# MainCircuit.net
KiCad netlist of a schematic drawn in Altium Designer
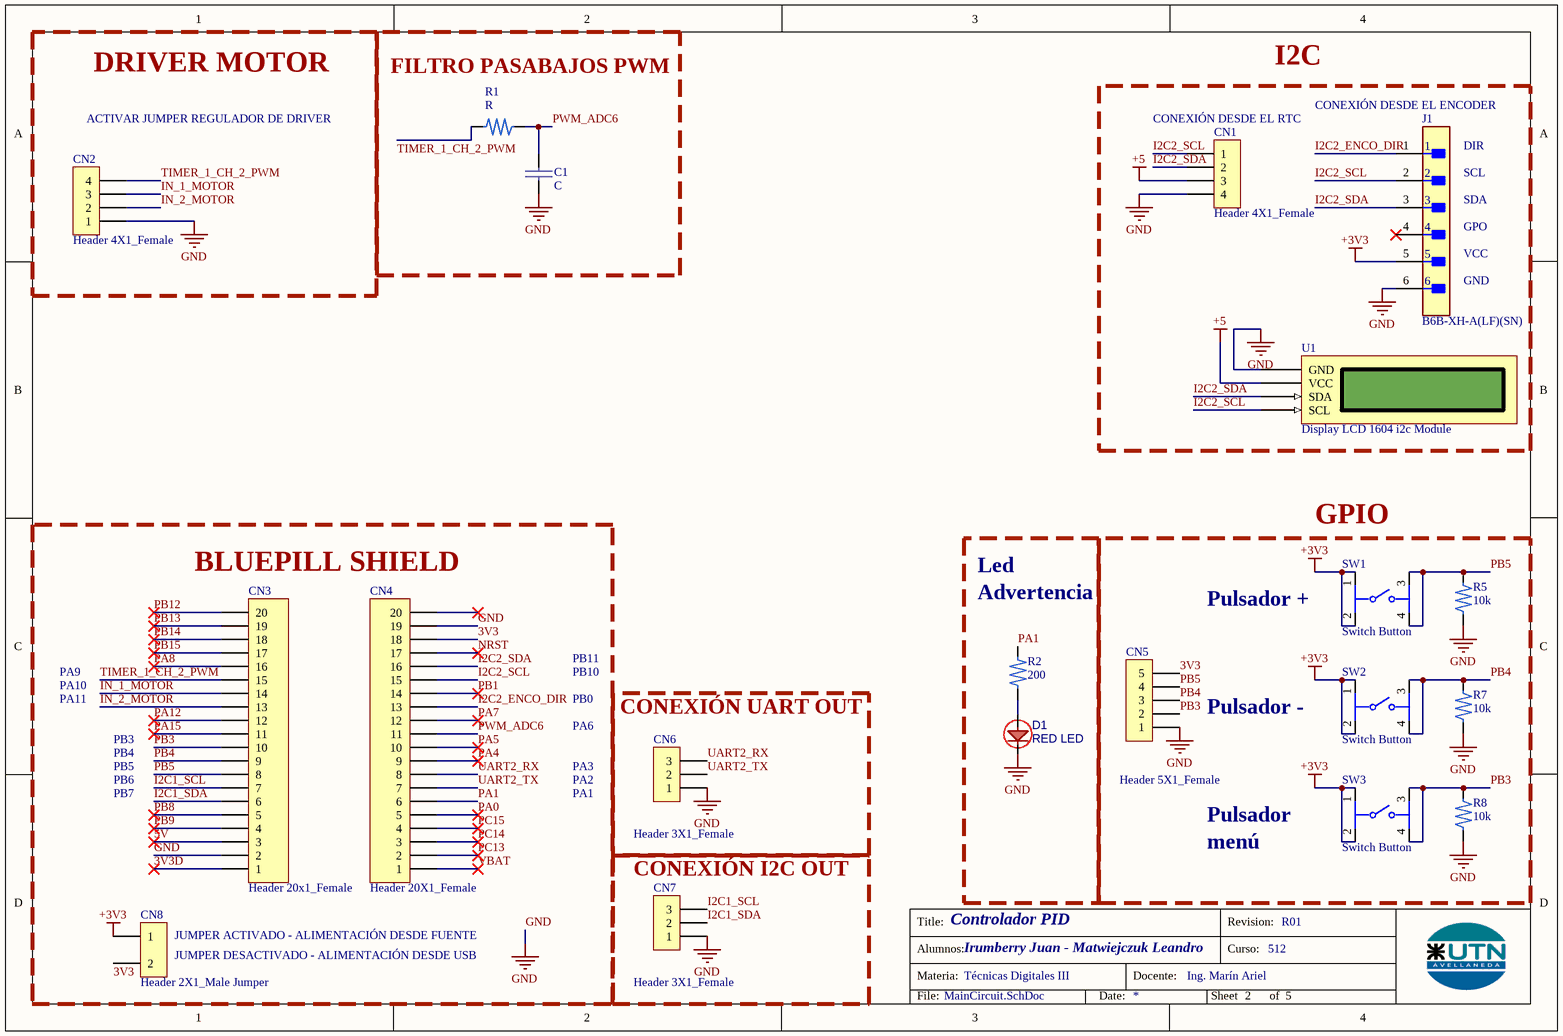
[diagram p0: MainCircuit.SchDoc]

(export (version "E")
  (design (tool "Eeschema 10.0.6"))
  (components
    (comp (ref "C1")
      (value "C")
      (footprint "CAP_Axial_0.2mm")
      (description "Non-Polarized Capacitor")
      (libsource (lib "ProyectoTD3") (part "CAP_NP"))
    )
    (comp (ref "CN1")
      (value "Header 4X1_Female")
      (footprint "1*4P_FEMALE")
      (description "Header, 4-Pin, Single row,female")
      (fields (field (name "PUBLISHER") "Altium Limited"))
      (libsource (lib "") (part "Header 4X1_Female_1"))
    )
    (comp (ref "CN2")
      (value "Header 4X1_Female")
      (footprint "1*4P_FEMALE")
      (description "Header, 4-Pin, Single row,female")
      (fields (field (name "PUBLISHER") "Altium Limited"))
      (libsource (lib "ProyectoTD3") (part "Header 4X1_Female"))
    )
    (comp (ref "CN3")
      (value "Header 20x1_Female")
      (footprint "1*20P_FEMALE")
      (description "Header, 16-Pin, Single row,female")
      (libsource (lib "ProyectoTD3") (part "Header 20x1_Female"))
    )
    (comp (ref "CN4")
      (value "Header 20X1_Female")
      (footprint "1*20P_FEMALE")
      (description "Header, 16-Pin, Single row,female")
      (libsource (lib "") (part "Header 20x1_Female_1"))
    )
    (comp (ref "CN5")
      (value "Header 5X1_Female")
      (footprint "1*5P_FEMALE")
      (description "Header, 5-Pin, Single row,female")
      (fields (field (name "PUBLISHER") "Altium Limited"))
      (libsource (lib "ProyectoTD3") (part "Header 5X1_Female"))
    )
    (comp (ref "CN6")
      (value "Header 3X1_Female")
      (footprint "1*3P_FEMALE")
      (description "Header, 3-Pin, Single row,female")
      (fields (field (name "PUBLISHER") "Altium Limited"))
      (libsource (lib "ProyectoTD3") (part "Header 3X1_Female"))
    )
    (comp (ref "CN7")
      (value "Header 3X1_Female")
      (footprint "1*3P_FEMALE")
      (description "Header, 3-Pin, Single row,female")
      (fields (field (name "PUBLISHER") "Altium Limited"))
      (libsource (lib "ProyectoTD3") (part "Header 3X1_Female"))
    )
    (comp (ref "CN8")
      (value "Header 2X1_Male Jumper")
      (footprint "JUMPER 2x1 PIN")
      (description "Header, 2-Pin, Single row,male")
      (fields (field (name "PUBLISHER") "Altium Limited"))
      (libsource (lib "ProyectoTD3") (part "Jumper 2 Pin"))
    )
    (comp (ref "D1")
      (value "RED LED")
      (footprint "LED_DIODE_3.9mm")
      (description "LED")
      (libsource (lib "ProyectoSchlib1") (part "LED"))
    )
    (comp (ref "J1")
      (value "B6B-XH-A(LF)(SN)")
      (footprint "JST 6 PIN CONNECTOR")
      (description "CONN HEADER VERT 6POS 2.5MM")
      (libsource (lib "ProyectoTD3") (part "JST 6 PIN"))
    )
    (comp (ref "R1")
      (value "R")
      (footprint "RES_AXIAL_3.2_6MM")
      (description "Through-hole Resistor")
      (libsource (lib "ProyectoTD3") (part "RES"))
    )
    (comp (ref "R2")
      (value "200")
      (footprint "RES_AXIAL_3.2_6MM")
      (description "Through-hole Resistor")
      (libsource (lib "ProyectoTD3") (part "RES"))
    )
    (comp (ref "R5")
      (value "10k")
      (footprint "RES_AXIAL_3.2_6MM")
      (description "Through-hole Resistor")
      (libsource (lib "ProyectoTD3") (part "RES"))
    )
    (comp (ref "R7")
      (value "10k")
      (footprint "RES_AXIAL_3.2_6MM")
      (description "Through-hole Resistor")
      (libsource (lib "ProyectoTD3") (part "RES"))
    )
    (comp (ref "R8")
      (value "10k")
      (footprint "RES_AXIAL_3.2_6MM")
      (description "Through-hole Resistor")
      (libsource (lib "ProyectoTD3") (part "RES"))
    )
    (comp (ref "SW1")
      (value "Switch Button")
      (footprint "SWITCH")
      (description "SWITCH TACTILE SPST-NO 0.05A 24V")
      (fields
        (field (name "OCTOPART") "https://octopart.com/1-1825910-4-te+connectivity-42270468")
        (field (name "MANUFACTURER") "TE Connectivity")
      )
      (libsource (lib "ProyectoTD3") (part "Switch Button"))
    )
    (comp (ref "SW2")
      (value "Switch Button")
      (footprint "SWITCH")
      (description "SWITCH TACTILE SPST-NO 0.05A 24V")
      (fields
        (field (name "OCTOPART") "https://octopart.com/1-1825910-4-te+connectivity-42270468")
        (field (name "MANUFACTURER") "TE Connectivity")
      )
      (libsource (lib "ProyectoTD3") (part "Switch Button"))
    )
    (comp (ref "SW3")
      (value "Switch Button")
      (footprint "SWITCH")
      (description "SWITCH TACTILE SPST-NO 0.05A 24V")
      (fields
        (field (name "OCTOPART") "https://octopart.com/1-1825910-4-te+connectivity-42270468")
        (field (name "MANUFACTURER") "TE Connectivity")
      )
      (libsource (lib "ProyectoTD3") (part "Switch Button"))
    )
    (comp (ref "U1")
      (value "Display LCD 1604 i2c Module")
      (footprint "1*4P_FEMALE")
      (libsource (lib "ProyectoTD3") (part "Display LCD 1604 i2c Module"))
    )
  )
  (nets
    (net (code "1") (name "+3V3") (class "Default")
      (node (ref "CN8") (pin "1") (pinfunction "1_1") (pintype "passive"))
      (node (ref "J1") (pin "5") (pinfunction "5_5") (pintype "passive"))
      (node (ref "SW1") (pin "1") (pinfunction "1_1") (pintype "passive"))
      (node (ref "SW1") (pin "2") (pinfunction "2_2") (pintype "passive"))
      (node (ref "SW2") (pin "1") (pinfunction "1_1") (pintype "passive"))
      (node (ref "SW2") (pin "2") (pinfunction "2_2") (pintype "passive"))
      (node (ref "SW3") (pin "1") (pinfunction "1_1") (pintype "passive"))
      (node (ref "SW3") (pin "2") (pinfunction "2_2") (pintype "passive"))
    )
    (net (code "2") (name "+5") (class "Default")
      (node (ref "CN1") (pin "3") (pinfunction "3_3") (pintype "passive"))
      (node (ref "U1") (pin "2") (pinfunction "VCC_2") (pintype "power_in"))
    )
    (net (code "3") (name "/3V3") (class "Default")
      (node (ref "CN4") (pin "18") (pinfunction "18_18") (pintype "passive"))
      (node (ref "CN5") (pin "5") (pinfunction "5_5") (pintype "passive"))
      (node (ref "CN8") (pin "2") (pinfunction "2_2") (pintype "passive"))
    )
    (net (code "4") (name "/3V3D") (class "Default")
      (node (ref "CN3") (pin "1") (pinfunction "1_1") (pintype "passive+no_connect"))
    )
    (net (code "5") (name "/5V") (class "Default")
      (node (ref "CN3") (pin "3") (pinfunction "3_3") (pintype "passive+no_connect"))
    )
    (net (code "6") (name "/I2C1_SCL") (class "Default")
      (node (ref "CN3") (pin "7") (pinfunction "7_7") (pintype "passive"))
      (node (ref "CN7") (pin "3") (pinfunction "3_3") (pintype "passive"))
    )
    (net (code "7") (name "/I2C1_SDA") (class "Default")
      (node (ref "CN3") (pin "6") (pinfunction "6_6") (pintype "passive"))
      (node (ref "CN7") (pin "2") (pinfunction "2_2") (pintype "passive"))
    )
    (net (code "8") (name "/I2C2_ENCO_DIR") (class "Default")
      (node (ref "CN4") (pin "13") (pinfunction "13_13") (pintype "passive"))
      (node (ref "J1") (pin "1") (pinfunction "1_1") (pintype "passive"))
    )
    (net (code "9") (name "/I2C2_SCL") (class "Default")
      (node (ref "CN1") (pin "1") (pinfunction "1_1") (pintype "passive"))
      (node (ref "CN4") (pin "15") (pinfunction "15_15") (pintype "passive"))
      (node (ref "J1") (pin "2") (pinfunction "2_2") (pintype "passive"))
      (node (ref "U1") (pin "4") (pinfunction "SCL_4") (pintype "input"))
    )
    (net (code "10") (name "/I2C2_SDA") (class "Default")
      (node (ref "CN1") (pin "2") (pinfunction "2_2") (pintype "passive"))
      (node (ref "CN4") (pin "16") (pinfunction "16_16") (pintype "passive"))
      (node (ref "J1") (pin "3") (pinfunction "3_3") (pintype "passive"))
      (node (ref "U1") (pin "3") (pinfunction "SDA_3") (pintype "input"))
    )
    (net (code "11") (name "/IN_1_MOTOR") (class "Default")
      (node (ref "CN2") (pin "3") (pinfunction "3_3") (pintype "passive"))
      (node (ref "CN3") (pin "14") (pinfunction "14_14") (pintype "passive"))
    )
    (net (code "12") (name "/IN_2_MOTOR") (class "Default")
      (node (ref "CN2") (pin "2") (pinfunction "2_2") (pintype "passive"))
      (node (ref "CN3") (pin "13") (pinfunction "13_13") (pintype "passive"))
    )
    (net (code "13") (name "/NRST") (class "Default")
      (node (ref "CN4") (pin "17") (pinfunction "17_17") (pintype "passive+no_connect"))
    )
    (net (code "14") (name "/PA0") (class "Default")
      (node (ref "CN4") (pin "5") (pinfunction "5_5") (pintype "passive+no_connect"))
    )
    (net (code "15") (name "/PA1") (class "Default")
      (node (ref "CN4") (pin "6") (pinfunction "6_6") (pintype "passive"))
      (node (ref "R2") (pin "2") (pinfunction "*_2") (pintype "passive"))
    )
    (net (code "16") (name "/PA4") (class "Default")
      (node (ref "CN4") (pin "9") (pinfunction "9_9") (pintype "passive+no_connect"))
    )
    (net (code "17") (name "/PA5") (class "Default")
      (node (ref "CN4") (pin "10") (pinfunction "10_10") (pintype "passive+no_connect"))
    )
    (net (code "18") (name "/PA7") (class "Default")
      (node (ref "CN4") (pin "12") (pinfunction "12_12") (pintype "passive+no_connect"))
    )
    (net (code "19") (name "/PA8") (class "Default")
      (node (ref "CN3") (pin "16") (pinfunction "16_16") (pintype "passive+no_connect"))
    )
    (net (code "20") (name "/PA12") (class "Default")
      (node (ref "CN3") (pin "12") (pinfunction "12_12") (pintype "passive+no_connect"))
    )
    (net (code "21") (name "/PA15") (class "Default")
      (node (ref "CN3") (pin "11") (pinfunction "11_11") (pintype "passive+no_connect"))
    )
    (net (code "22") (name "/PB1") (class "Default")
      (node (ref "CN4") (pin "14") (pinfunction "14_14") (pintype "passive+no_connect"))
    )
    (net (code "23") (name "/PB3") (class "Default")
      (node (ref "CN3") (pin "10") (pinfunction "10_10") (pintype "passive"))
      (node (ref "CN5") (pin "2") (pinfunction "2_2") (pintype "passive"))
      (node (ref "R8") (pin "2") (pinfunction "*_2") (pintype "passive"))
      (node (ref "SW3") (pin "3") (pinfunction "3_3") (pintype "passive"))
      (node (ref "SW3") (pin "4") (pinfunction "4_4") (pintype "passive"))
    )
    (net (code "24") (name "/PB4") (class "Default")
      (node (ref "CN3") (pin "9") (pinfunction "9_9") (pintype "passive"))
      (node (ref "CN5") (pin "3") (pinfunction "3_3") (pintype "passive"))
      (node (ref "R7") (pin "2") (pinfunction "*_2") (pintype "passive"))
      (node (ref "SW2") (pin "3") (pinfunction "3_3") (pintype "passive"))
      (node (ref "SW2") (pin "4") (pinfunction "4_4") (pintype "passive"))
    )
    (net (code "25") (name "/PB5") (class "Default")
      (node (ref "CN3") (pin "8") (pinfunction "8_8") (pintype "passive"))
      (node (ref "CN5") (pin "4") (pinfunction "4_4") (pintype "passive"))
      (node (ref "R5") (pin "2") (pinfunction "*_2") (pintype "passive"))
      (node (ref "SW1") (pin "3") (pinfunction "3_3") (pintype "passive"))
      (node (ref "SW1") (pin "4") (pinfunction "4_4") (pintype "passive"))
    )
    (net (code "26") (name "/PB8") (class "Default")
      (node (ref "CN3") (pin "5") (pinfunction "5_5") (pintype "passive+no_connect"))
    )
    (net (code "27") (name "/PB9") (class "Default")
      (node (ref "CN3") (pin "4") (pinfunction "4_4") (pintype "passive+no_connect"))
    )
    (net (code "28") (name "/PB12") (class "Default")
      (node (ref "CN3") (pin "20") (pinfunction "20_20") (pintype "passive+no_connect"))
    )
    (net (code "29") (name "/PB13") (class "Default")
      (node (ref "CN3") (pin "19") (pinfunction "19_19") (pintype "passive+no_connect"))
    )
    (net (code "30") (name "/PB14") (class "Default")
      (node (ref "CN3") (pin "18") (pinfunction "18_18") (pintype "passive+no_connect"))
    )
    (net (code "31") (name "/PB15") (class "Default")
      (node (ref "CN3") (pin "17") (pinfunction "17_17") (pintype "passive+no_connect"))
    )
    (net (code "32") (name "/PC13") (class "Default")
      (node (ref "CN4") (pin "2") (pinfunction "2_2") (pintype "passive+no_connect"))
    )
    (net (code "33") (name "/PC14") (class "Default")
      (node (ref "CN4") (pin "3") (pinfunction "3_3") (pintype "passive+no_connect"))
    )
    (net (code "34") (name "/PC15") (class "Default")
      (node (ref "CN4") (pin "4") (pinfunction "4_4") (pintype "passive+no_connect"))
    )
    (net (code "35") (name "/PWM_ADC6") (class "Default")
      (node (ref "C1") (pin "1") (pinfunction "1_1") (pintype "passive"))
      (node (ref "CN4") (pin "11") (pinfunction "11_11") (pintype "passive"))
      (node (ref "R1") (pin "2") (pinfunction "*_2") (pintype "passive"))
    )
    (net (code "36") (name "/TIMER_1_CH_2_PWM") (class "Default")
      (node (ref "CN2") (pin "4") (pinfunction "4_4") (pintype "passive"))
      (node (ref "CN3") (pin "15") (pinfunction "15_15") (pintype "passive"))
      (node (ref "R1") (pin "1") (pinfunction "*_1") (pintype "passive"))
    )
    (net (code "37") (name "/UART2_RX") (class "Default")
      (node (ref "CN4") (pin "8") (pinfunction "8_8") (pintype "passive"))
      (node (ref "CN6") (pin "3") (pinfunction "3_3") (pintype "passive"))
    )
    (net (code "38") (name "/UART2_TX") (class "Default")
      (node (ref "CN4") (pin "7") (pinfunction "7_7") (pintype "passive"))
      (node (ref "CN6") (pin "2") (pinfunction "2_2") (pintype "passive"))
    )
    (net (code "39") (name "/VBAT") (class "Default")
      (node (ref "CN4") (pin "1") (pinfunction "1_1") (pintype "passive+no_connect"))
    )
    (net (code "40") (name "GND") (class "Default")
      (node (ref "C1") (pin "2") (pinfunction "2_2") (pintype "passive"))
      (node (ref "CN1") (pin "4") (pinfunction "4_4") (pintype "passive"))
      (node (ref "CN2") (pin "1") (pinfunction "1_1") (pintype "passive"))
      (node (ref "CN3") (pin "2") (pinfunction "2_2") (pintype "passive"))
      (node (ref "CN4") (pin "19") (pinfunction "19_19") (pintype "passive"))
      (node (ref "CN5") (pin "1") (pinfunction "1_1") (pintype "passive"))
      (node (ref "CN6") (pin "1") (pinfunction "1_1") (pintype "passive"))
      (node (ref "CN7") (pin "1") (pinfunction "1_1") (pintype "passive"))
      (node (ref "D1") (pin "K") (pinfunction "K_K") (pintype "passive"))
      (node (ref "J1") (pin "6") (pinfunction "6_6") (pintype "passive"))
      (node (ref "R5") (pin "1") (pinfunction "*_1") (pintype "passive"))
      (node (ref "R7") (pin "1") (pinfunction "*_1") (pintype "passive"))
      (node (ref "R8") (pin "1") (pinfunction "*_1") (pintype "passive"))
      (node (ref "U1") (pin "1") (pinfunction "GND_1") (pintype "power_in"))
    )
    (net (code "41") (name "Net-(D1-PadA)") (class "Default")
      (node (ref "D1") (pin "A") (pinfunction "A_A") (pintype "passive"))
      (node (ref "R2") (pin "1") (pinfunction "*_1") (pintype "passive"))
    )
    (net (code "42") (name "unconnected-(CN4-Pad20)") (class "Default")
      (node (ref "CN4") (pin "20") (pinfunction "20_20") (pintype "passive+no_connect"))
    )
    (net (code "43") (name "unconnected-(J1-Pad4)") (class "Default")
      (node (ref "J1") (pin "4") (pinfunction "4_4") (pintype "passive+no_connect"))
    )
  )
)
